# Head_Lights.net
KiCad netlist of a schematic drawn in EAGLE
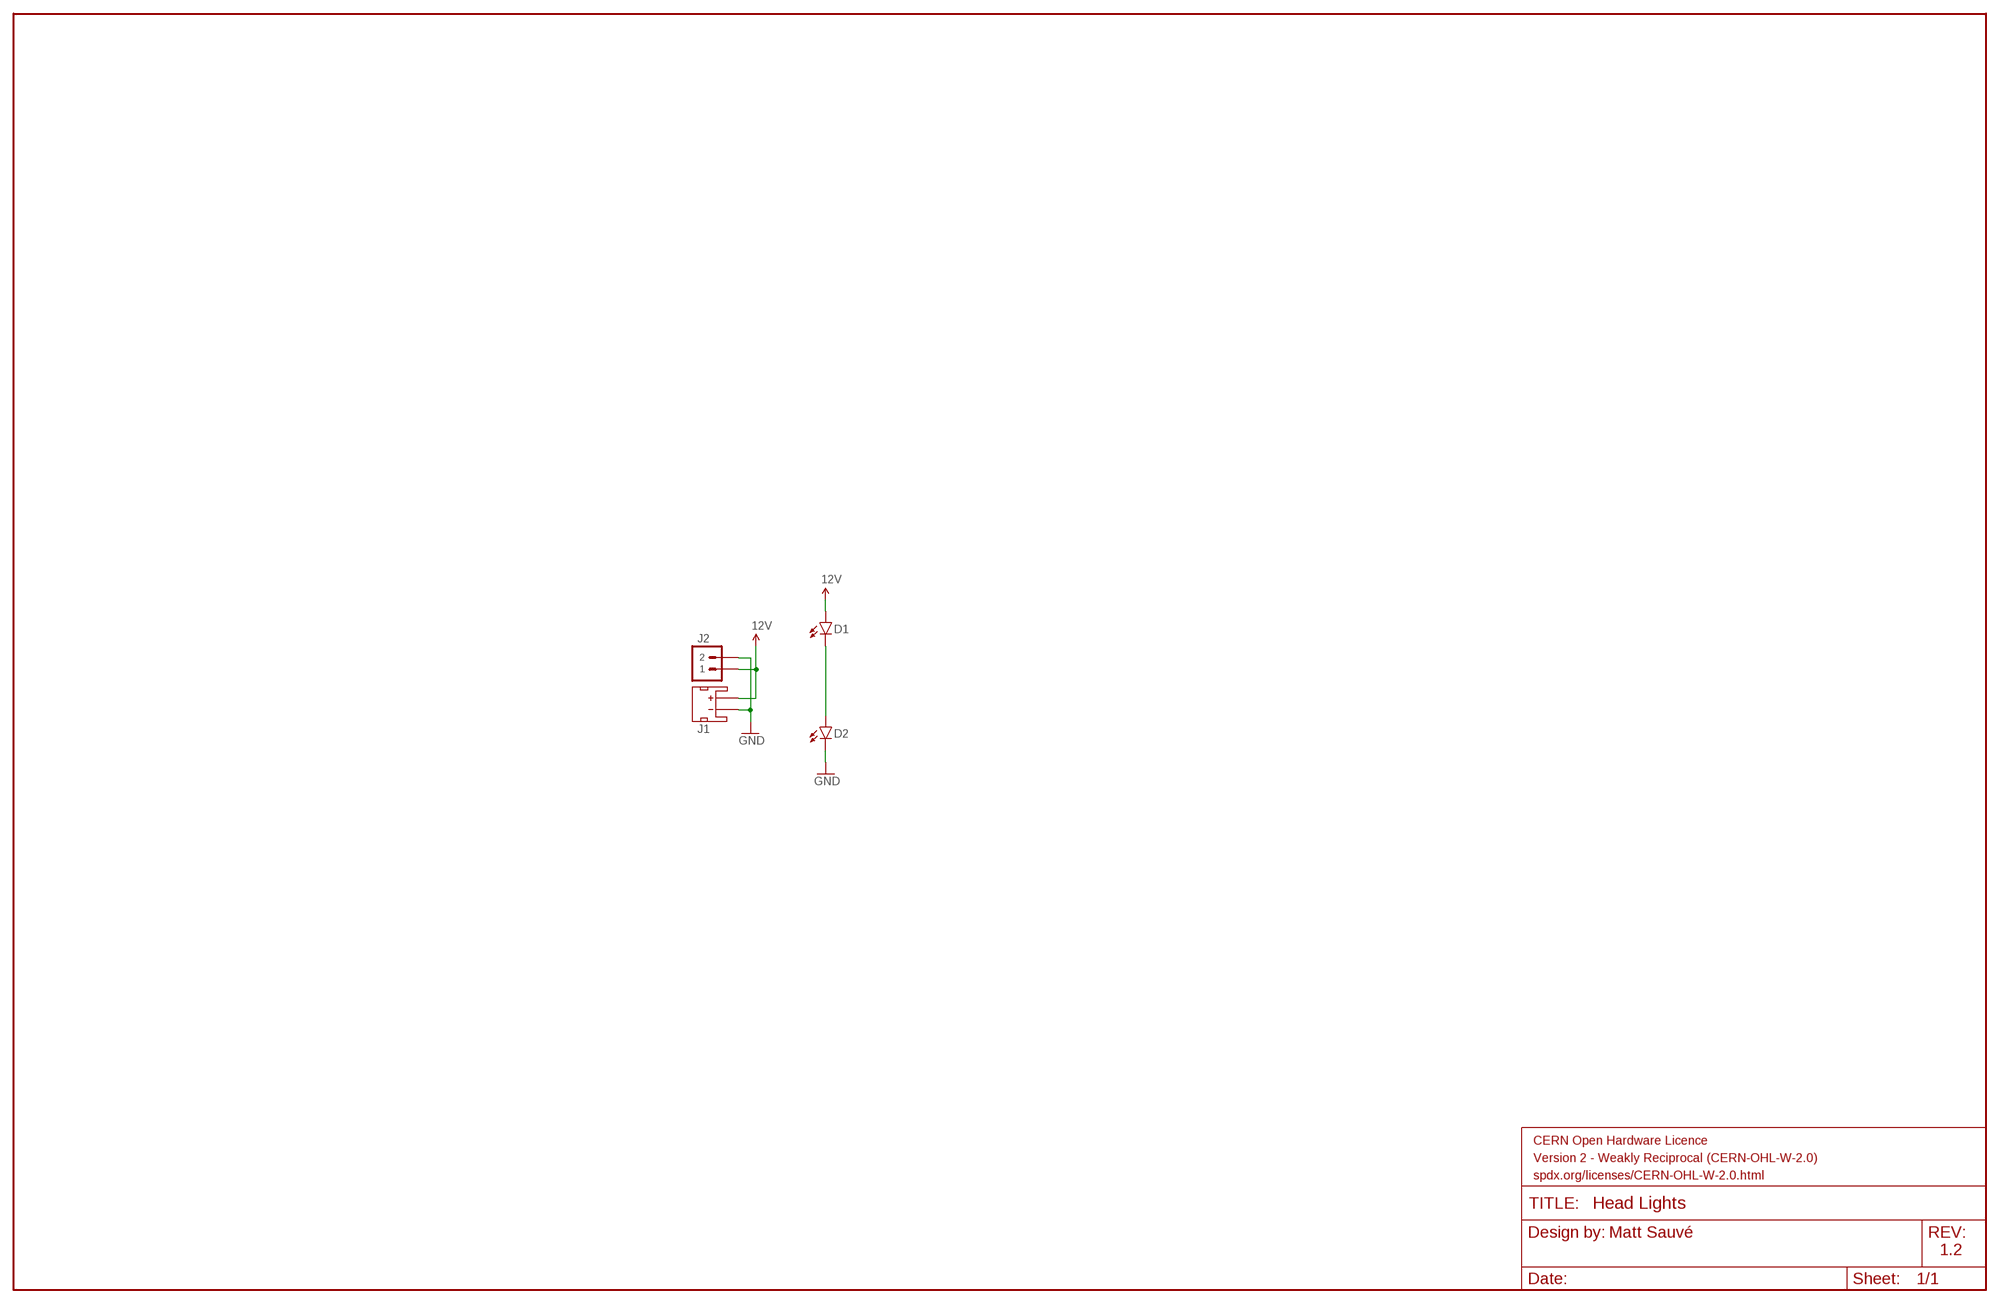
[diagram p0: schematic, sheet 1]

(export (version "E")
  (design (tool "Eeschema 10.0.6"))
  (components
    (comp (ref "D1")
      (value "WHITE_LUXEON_LED")
      (footprint "eagle-import:1414")
      (libsource (lib "eagle-import") (part "WHITE_LUXEON_LED"))
    )
    (comp (ref "D2")
      (value "WHITE_LUXEON_LED")
      (footprint "eagle-import:1414")
      (libsource (lib "eagle-import") (part "WHITE_LUXEON_LED"))
    )
    (comp (ref "FRAME1")
      (value "FRAME-LEDGER_CERN_WEAK")
      (footprint "eagle-import:CERN_WEAK")
      (libsource (lib "eagle-import") (part "FRAME-LEDGER_CERN_WEAK"))
    )
    (comp (ref "J1")
      (value "JST_2MM_MALE")
      (footprint "eagle-import:JST-2-SMD")
      (libsource (lib "eagle-import") (part "JST_2MM_MALE"))
    )
    (comp (ref "J2")
      (value "JST_PH_2POS")
      (footprint "eagle-import:JST_PH_2POS")
      (libsource (lib "eagle-import") (part "JST_PH_2POS"))
    )
  )
  (nets
    (net (code "1") (name "12V") (class "Default")
      (node (ref "D1") (pin "P$1") (pinfunction "A_P$1") (pintype "passive"))
      (node (ref "J1") (pin "2") (pinfunction "+_2") (pintype "bidirectional"))
      (node (ref "J2") (pin "1") (pinfunction "1_1") (pintype "passive"))
    )
    (net (code "2") (name "GND") (class "Default")
      (node (ref "D2") (pin "P$2") (pinfunction "C_P$2") (pintype "passive"))
      (node (ref "J1") (pin "1") (pinfunction "-_1") (pintype "bidirectional"))
      (node (ref "J2") (pin "2") (pinfunction "2_2") (pintype "passive"))
    )
    (net (code "3") (name "Net-(D1-C)") (class "Default")
      (node (ref "D1") (pin "P$2") (pinfunction "C_P$2") (pintype "passive"))
      (node (ref "D2") (pin "P$1") (pinfunction "A_P$1") (pintype "passive"))
    )
    (net (code "4") (name "unconnected-(J1-PAD1-PadNC1)") (class "Default")
      (node (ref "J1") (pin "NC1") (pinfunction "PAD1_NC1") (pintype "bidirectional"))
    )
    (net (code "5") (name "unconnected-(J1-PAD2-PadNC2)") (class "Default")
      (node (ref "J1") (pin "NC2") (pinfunction "PAD2_NC2") (pintype "bidirectional"))
    )
  )
)
